# RADC-BackupPower-S08-V00.net
KiCad netlist of a schematic drawn in Altium Designer
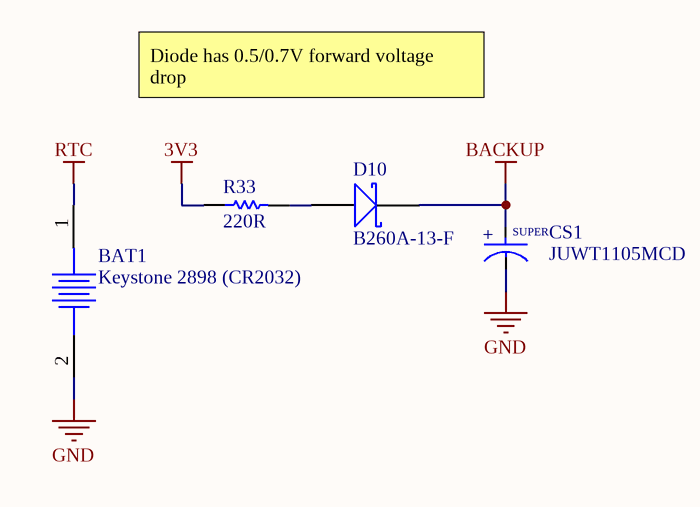
[diagram p0: RADC-BackupPower-S08-V00.SchDoc]

(export (version "E")
  (design (tool "Eeschema 10.0.6"))
  (components
    (comp (ref "BAT1")
      (value "Keystone 2898 (CR2032)")
      (footprint "Keystone 2898")
      (description "Battery Retainer Coin, 20.0mm 1 Cell SMD (SMT) Tab")
      (libsource (lib "QUTMS_PowerSupplyLibrary") (part "Keystone 2898"))
    )
    (comp (ref "CS1")
      (value "JUWT1105MCD")
      (footprint "CAP_ALU_6.3mmD_9mmL")
      (description "1F (EDLC) Supercapacitor 2.7V Radial, Can 4Ohm @ 1kHz 1000 Hrs @ 70°C")
      (libsource (lib "StandardCapacitors") (part "JUWT1105MCD"))
    )
    (comp (ref "D10")
      (value "B260A-13-F")
      (footprint "SMA")
      (description "Diode, Schottky Barrier Rectifier, 60 V, 2 A, B260A-13-F")
      (libsource (lib "QUTMS_DiodeLibrary") (part "B260A-13-F"))
    )
    (comp (ref "R33")
      (value "220R")
      (footprint "Res_ThinFilm_0603")
      (description "Resistor, SMD, 220R, 0.1W, 5%, 0603")
      (libsource (lib "StandardResistors") (part "220R 5% 0603"))
    )
  )
  (nets
    (net (code "1") (name "3V3") (class "Default")
      (node (ref "R33") (pin "1") (pinfunction "1_1") (pintype "passive"))
    )
    (net (code "2") (name "BACKUP") (class "Default")
      (node (ref "CS1") (pin "A") (pinfunction "A_A") (pintype "passive"))
      (node (ref "D10") (pin "K") (pinfunction "K_K") (pintype "passive"))
    )
    (net (code "3") (name "GND") (class "Default")
      (node (ref "BAT1") (pin "2") (pinfunction "1_2") (pintype "passive"))
      (node (ref "CS1") (pin "K") (pinfunction "K_K") (pintype "passive"))
    )
    (net (code "4") (name "Net-(D10-PadA)") (class "Default")
      (node (ref "D10") (pin "A") (pinfunction "A_A") (pintype "passive"))
      (node (ref "R33") (pin "2") (pinfunction "2_2") (pintype "passive"))
    )
    (net (code "5") (name "RTC") (class "Default")
      (node (ref "BAT1") (pin "1") (pinfunction "0_1") (pintype "passive"))
    )
  )
)
